# Geiger_Pwr_LM3478.net
KiCad netlist of a schematic drawn in Altium Designer
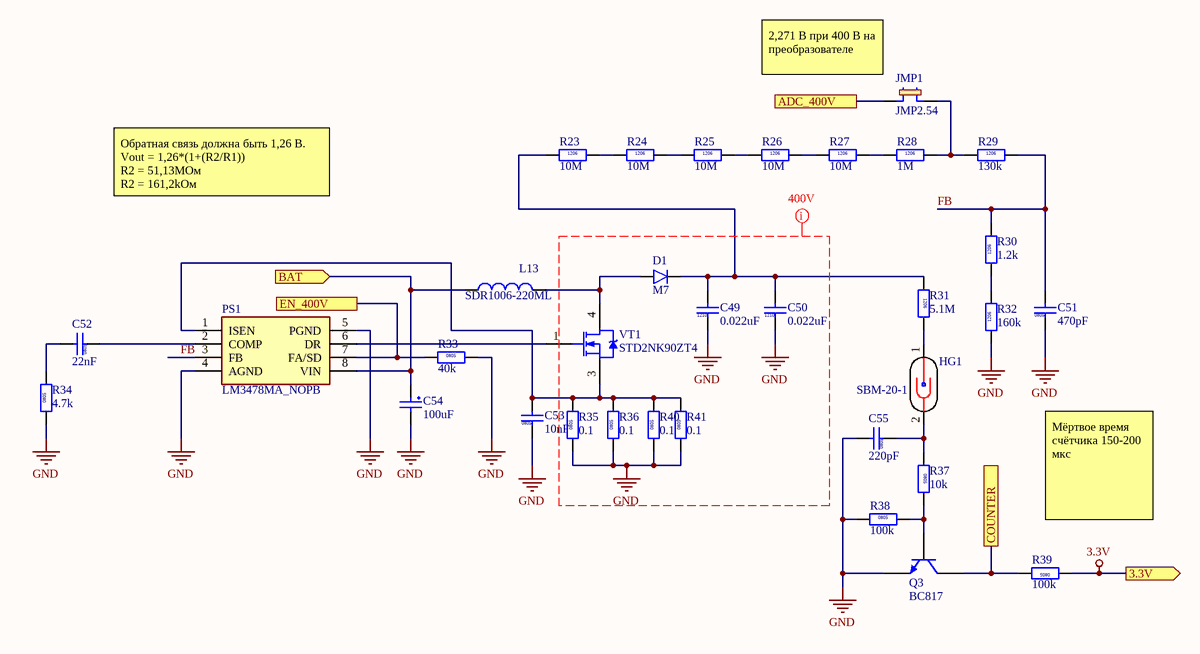
[diagram p0: Geiger_Pwr_LM3478.SchDoc]

(export (version "E")
  (design (tool "Eeschema 10.0.6"))
  (components
    (comp (ref "C49")
      (value "0.022uF")
      (footprint "CAPC3225-1210L")
      (description "Capacitor 1210")
      (fields (field (name "Comment") "CAPC_1210"))
      (libsource (lib "Passive") (part "CAPC_1210"))
    )
    (comp (ref "C50")
      (value "0.022uF")
      (footprint "CAPC3225-1210L")
      (description "Capacitor 1210")
      (fields (field (name "Comment") "CAPC_1210"))
      (libsource (lib "Passive") (part "CAPC_1210"))
    )
    (comp (ref "C51")
      (value "470pF")
      (footprint "CAPC2012-0805M")
      (description "Capacitor 0805")
      (fields (field (name "Comment") "CAPC_0805"))
      (libsource (lib "Passive") (part "CAPC_0805"))
    )
    (comp (ref "C52")
      (value "22nF")
      (footprint "CAPC2012-0805M")
      (description "Capacitor 0805")
      (fields (field (name "Comment") "CAPC_0805"))
      (libsource (lib "Passive") (part "CAPC_0805"))
    )
    (comp (ref "C53")
      (value "10nF")
      (footprint "CAPC2012-0805M")
      (description "Capacitor 0805")
      (fields (field (name "Comment") "CAPC_0805"))
      (libsource (lib "Passive") (part "CAPC_0805"))
    )
    (comp (ref "C54")
      (value "100uF")
      (footprint "ECAP511")
      (description "Capacitor electrolytic 2.5 mm pitch, 5*11 body")
      (fields (field (name "Comment") "ECAP-511"))
      (libsource (lib "Passive") (part "ECAP-511"))
    )
    (comp (ref "C55")
      (value "220pF")
      (footprint "CAPC2012-0805M")
      (description "Capacitor 0805")
      (fields (field (name "Comment") "CAPC_0805"))
      (libsource (lib "Passive") (part "CAPC_0805"))
    )
    (comp (ref "D1")
      (value "M7")
      (footprint "DIOM5026X262N")
      (description "Diode")
      (fields (field (name "MANUFACTURER_PART_NUMBER") "SS34A"))
      (libsource (lib "M7 diode") (part "M7"))
    )
    (comp (ref "HG1")
      (value "SBM-20-1")
      (footprint "SBM-20-1")
      (libsource (lib "Bogdanov") (part "SBM-20-1"))
    )
    (comp (ref "JMP1")
      (value "JMP2.54")
      (footprint "JMP2.54")
      (description "2.54mm single jumper")
      (libsource (lib "Connectors") (part "JMP2.54"))
    )
    (comp (ref "L13")
      (value "SDR1006-220ML")
      (footprint "Bogdanov:SDR1006")
      (description "Connector")
      (fields
        (field (name "MOUSER PART NUMBER") "652-SDR1006-220ML")
        (field (name "RS PART NUMBER") "7361349P")
      )
      (libsource (lib "Bogdanov") (part "SDR1006-220ML"))
    )
    (comp (ref "PS1")
      (value "LM3478MA_NOPB")
      (footprint "SamacSys:SOIC127P600X175-8N")
      (description "Power Supply")
      (fields
        (field (name "MANUFACTURER_PART_NUMBER") "LM3478MA/NOPB")
        (field (name "MOUSER PART NUMBER") "926-LM3478MA/NOPB")
      )
      (libsource (lib "*") (part "LM3478MA_NOPB"))
    )
    (comp (ref "Q3")
      (value "BC817")
      (footprint "SOT23-3M")
      (description "BC817 NPN Transistor")
      (libsource (lib "Discrete") (part "BC817"))
    )
    (comp (ref "R23")
      (value "10M")
      (footprint "RESC3216-1206M")
      (description "Resistor 1206")
      (fields (field (name "Comment") "RESC_1206_R"))
      (libsource (lib "Passive") (part "RESC_1206_R"))
    )
    (comp (ref "R24")
      (value "10M")
      (footprint "RESC3216-1206M")
      (description "Resistor 1206")
      (fields (field (name "Comment") "RESC_1206_R"))
      (libsource (lib "Passive") (part "RESC_1206_R"))
    )
    (comp (ref "R25")
      (value "10M")
      (footprint "RESC3216-1206M")
      (description "Resistor 1206")
      (fields (field (name "Comment") "RESC_1206_R"))
      (libsource (lib "Passive") (part "RESC_1206_R"))
    )
    (comp (ref "R26")
      (value "10M")
      (footprint "RESC3216-1206M")
      (description "Resistor 1206")
      (fields (field (name "Comment") "RESC_1206_R"))
      (libsource (lib "Passive") (part "RESC_1206_R"))
    )
    (comp (ref "R27")
      (value "10M")
      (footprint "RESC3216-1206M")
      (description "Resistor 1206")
      (fields (field (name "Comment") "RESC_1206_R"))
      (libsource (lib "Passive") (part "RESC_1206_R"))
    )
    (comp (ref "R28")
      (value "1M")
      (footprint "RESC3216-1206M")
      (description "Resistor 1206")
      (fields (field (name "Comment") "RESC_1206_R"))
      (libsource (lib "Passive") (part "RESC_1206_R"))
    )
    (comp (ref "R29")
      (value "130k")
      (footprint "RESC3216-1206M")
      (description "Resistor 1206")
      (fields (field (name "Comment") "RESC_1206_R"))
      (libsource (lib "Passive") (part "RESC_1206_R"))
    )
    (comp (ref "R30")
      (value "1.2k")
      (footprint "RESC3216-1206M")
      (description "Resistor 1206")
      (fields (field (name "Comment") "RESC_1206_R"))
      (libsource (lib "") (part "RESC_1206_R_1"))
    )
    (comp (ref "R31")
      (value "5.1M")
      (footprint "RESC3216-1206M")
      (description "Resistor 1206")
      (fields (field (name "Comment") "RESC_1206_R"))
      (libsource (lib "") (part "RESC_1206_R_2"))
    )
    (comp (ref "R32")
      (value "160k")
      (footprint "RESC3216-1206M")
      (description "Resistor 1206")
      (fields (field (name "Comment") "RESC_1206_R"))
      (libsource (lib "") (part "RESC_1206_R_1"))
    )
    (comp (ref "R33")
      (value "40k")
      (footprint "RESC2012-0805M")
      (description "Resistor 0805")
      (fields (field (name "Comment") "RESC_0805_R"))
      (libsource (lib "Passive") (part "RESC_0805_R"))
    )
    (comp (ref "R34")
      (value "4.7k")
      (footprint "RESC2012-0805M")
      (description "Resistor 0805")
      (fields (field (name "Comment") "RESC_0805_R"))
      (libsource (lib "") (part "RESC_0805_R_1"))
    )
    (comp (ref "R35")
      (value "0.1")
      (footprint "RESC2012-0805M")
      (description "Resistor 0805")
      (fields (field (name "Comment") "RESC_0805_R"))
      (libsource (lib "") (part "RESC_0805_R_1"))
    )
    (comp (ref "R36")
      (value "0.1")
      (footprint "RESC2012-0805M")
      (description "Resistor 0805")
      (fields (field (name "Comment") "RESC_0805_R"))
      (libsource (lib "") (part "RESC_0805_R_1"))
    )
    (comp (ref "R37")
      (value "10k")
      (footprint "RESC2012-0805M")
      (description "Resistor 0805")
      (fields (field (name "Comment") "RESC_0805_R"))
      (libsource (lib "") (part "RESC_0805_R_2"))
    )
    (comp (ref "R38")
      (value "100k")
      (footprint "RESC2012-0805M")
      (description "Resistor 0805")
      (fields (field (name "Comment") "RESC_0805_R"))
      (libsource (lib "Passive") (part "RESC_0805_R"))
    )
    (comp (ref "R39")
      (value "100k")
      (footprint "RESC2012-0805M")
      (description "Resistor 0805")
      (fields (field (name "Comment") "RESC_0805_R"))
      (libsource (lib "") (part "RESC_0805_R_3"))
    )
    (comp (ref "R40")
      (value "0.1")
      (footprint "RESC2012-0805M")
      (description "Resistor 0805")
      (fields (field (name "Comment") "RESC_0805_R"))
      (libsource (lib "") (part "RESC_0805_R_1"))
    )
    (comp (ref "R41")
      (value "0.1")
      (footprint "RESC2012-0805M")
      (description "Resistor 0805")
      (fields (field (name "Comment") "RESC_0805_R"))
      (libsource (lib "") (part "RESC_0805_R_1"))
    )
    (comp (ref "VT1")
      (value "STD2NK90ZT4")
      (footprint "SamacSys:TO228P972X240-3N")
      (description "Integrated Circuit")
      (fields (field (name "MOUSER PART NUMBER") "511-STD2NK90Z") (field (name "RS PART NUMBER") "6875100P"))
      (libsource (lib "Bogdanov") (part "STD2NK90ZT4"))
    )
  )
  (nets
    (net (code "1") (name "/ADC_400V") (class "Default")
      (node (ref "JMP1") (pin "1") (pinfunction "1_1") (pintype "power_in"))
    )
    (net (code "2") (name "/BAT") (class "Default")
      (node (ref "C54") (pin "1") (pinfunction "1_1") (pintype "passive"))
      (node (ref "L13") (pin "1") (pinfunction "1_1") (pintype "passive"))
      (node (ref "PS1") (pin "8") (pinfunction "VIN_8") (pintype "passive"))
    )
    (net (code "3") (name "/COUNTER") (class "Default")
      (node (ref "Q3") (pin "3") (pinfunction "C_3") (pintype "passive"))
      (node (ref "R39") (pin "2") (pinfunction "2_2") (pintype "passive"))
    )
    (net (code "4") (name "/EN_400V") (class "Default")
      (node (ref "PS1") (pin "7") (pinfunction "FA/SD_7") (pintype "passive"))
      (node (ref "R33") (pin "1") (pinfunction "1_1") (pintype "passive"))
    )
    (net (code "5") (name "/FB") (class "Default")
      (node (ref "C51") (pin "2") (pinfunction "2_2") (pintype "passive"))
      (node (ref "PS1") (pin "3") (pinfunction "FB_3") (pintype "passive"))
      (node (ref "R29") (pin "2") (pinfunction "2_2") (pintype "passive"))
      (node (ref "R30") (pin "2") (pinfunction "2_2") (pintype "passive"))
    )
    (net (code "6") (name "3.3V") (class "Default")
      (node (ref "R39") (pin "1") (pinfunction "1_1") (pintype "passive"))
    )
    (net (code "7") (name "GND") (class "Default")
      (node (ref "C49") (pin "1") (pinfunction "1_1") (pintype "passive"))
      (node (ref "C50") (pin "1") (pinfunction "1_1") (pintype "passive"))
      (node (ref "C51") (pin "1") (pinfunction "1_1") (pintype "passive"))
      (node (ref "C53") (pin "1") (pinfunction "1_1") (pintype "passive"))
      (node (ref "C54") (pin "2") (pinfunction "2_2") (pintype "passive"))
      (node (ref "C55") (pin "2") (pinfunction "2_2") (pintype "passive"))
      (node (ref "PS1") (pin "4") (pinfunction "AGND_4") (pintype "passive"))
      (node (ref "PS1") (pin "5") (pinfunction "PGND_5") (pintype "passive"))
      (node (ref "Q3") (pin "2") (pinfunction "E_2") (pintype "passive"))
      (node (ref "R32") (pin "1") (pinfunction "1_1") (pintype "passive"))
      (node (ref "R33") (pin "2") (pinfunction "2_2") (pintype "passive"))
      (node (ref "R34") (pin "1") (pinfunction "1_1") (pintype "passive"))
      (node (ref "R35") (pin "1") (pinfunction "1_1") (pintype "passive"))
      (node (ref "R36") (pin "1") (pinfunction "1_1") (pintype "passive"))
      (node (ref "R38") (pin "1") (pinfunction "1_1") (pintype "passive"))
      (node (ref "R40") (pin "1") (pinfunction "1_1") (pintype "passive"))
      (node (ref "R41") (pin "1") (pinfunction "1_1") (pintype "passive"))
    )
    (net (code "8") (name "Net-(C52-Pad2)") (class "Default")
      (node (ref "C52") (pin "2") (pinfunction "2_2") (pintype "passive"))
      (node (ref "R34") (pin "2") (pinfunction "2_2") (pintype "passive"))
    )
    (net (code "9") (name "Net-(D1-A)") (class "Default")
      (node (ref "D1") (pin "2") (pinfunction "A_2") (pintype "passive"))
      (node (ref "L13") (pin "2") (pinfunction "2_2") (pintype "passive"))
      (node (ref "VT1") (pin "4") (pinfunction "D_4") (pintype "passive"))
    )
    (net (code "10") (name "Net-(D1-K)") (class "Default")
      (node (ref "C49") (pin "2") (pinfunction "2_2") (pintype "passive"))
      (node (ref "C50") (pin "2") (pinfunction "2_2") (pintype "passive"))
      (node (ref "D1") (pin "1") (pinfunction "K_1") (pintype "passive"))
      (node (ref "R23") (pin "1") (pinfunction "1_1") (pintype "passive"))
      (node (ref "R31") (pin "1") (pinfunction "1_1") (pintype "passive"))
    )
    (net (code "11") (name "Net-(HG1-A)") (class "Default")
      (node (ref "HG1") (pin "1") (pinfunction "A_1") (pintype "passive"))
      (node (ref "R31") (pin "2") (pinfunction "2_2") (pintype "passive"))
    )
    (net (code "12") (name "Net-(HG1-K)") (class "Default")
      (node (ref "C55") (pin "1") (pinfunction "1_1") (pintype "passive"))
      (node (ref "HG1") (pin "2") (pinfunction "K_2") (pintype "passive"))
      (node (ref "R37") (pin "1") (pinfunction "1_1") (pintype "passive"))
    )
    (net (code "13") (name "Net-(JMP1-Pad2)") (class "Default")
      (node (ref "JMP1") (pin "2") (pinfunction "2_2") (pintype "power_in"))
      (node (ref "R28") (pin "2") (pinfunction "2_2") (pintype "passive"))
      (node (ref "R29") (pin "1") (pinfunction "1_1") (pintype "passive"))
    )
    (net (code "14") (name "Net-(PS1-COMP)") (class "Default")
      (node (ref "C52") (pin "1") (pinfunction "1_1") (pintype "passive"))
      (node (ref "PS1") (pin "2") (pinfunction "COMP_2") (pintype "passive"))
    )
    (net (code "15") (name "Net-(PS1-DR)") (class "Default")
      (node (ref "PS1") (pin "6") (pinfunction "DR_6") (pintype "passive"))
      (node (ref "VT1") (pin "1") (pinfunction "G_1") (pintype "passive"))
    )
    (net (code "16") (name "Net-(PS1-ISEN)") (class "Default")
      (node (ref "C53") (pin "2") (pinfunction "2_2") (pintype "passive"))
      (node (ref "PS1") (pin "1") (pinfunction "ISEN_1") (pintype "passive"))
      (node (ref "R35") (pin "2") (pinfunction "2_2") (pintype "passive"))
      (node (ref "R36") (pin "2") (pinfunction "2_2") (pintype "passive"))
      (node (ref "R40") (pin "2") (pinfunction "2_2") (pintype "passive"))
      (node (ref "R41") (pin "2") (pinfunction "2_2") (pintype "passive"))
      (node (ref "VT1") (pin "3") (pinfunction "S_3") (pintype "passive"))
    )
    (net (code "17") (name "Net-(Q3-B)") (class "Default")
      (node (ref "Q3") (pin "1") (pinfunction "B_1") (pintype "passive"))
      (node (ref "R37") (pin "2") (pinfunction "2_2") (pintype "passive"))
      (node (ref "R38") (pin "2") (pinfunction "2_2") (pintype "passive"))
    )
    (net (code "18") (name "Net-(R23-Pad2)") (class "Default")
      (node (ref "R23") (pin "2") (pinfunction "2_2") (pintype "passive"))
      (node (ref "R24") (pin "1") (pinfunction "1_1") (pintype "passive"))
    )
    (net (code "19") (name "Net-(R24-Pad2)") (class "Default")
      (node (ref "R24") (pin "2") (pinfunction "2_2") (pintype "passive"))
      (node (ref "R25") (pin "1") (pinfunction "1_1") (pintype "passive"))
    )
    (net (code "20") (name "Net-(R25-Pad2)") (class "Default")
      (node (ref "R25") (pin "2") (pinfunction "2_2") (pintype "passive"))
      (node (ref "R26") (pin "1") (pinfunction "1_1") (pintype "passive"))
    )
    (net (code "21") (name "Net-(R26-Pad2)") (class "Default")
      (node (ref "R26") (pin "2") (pinfunction "2_2") (pintype "passive"))
      (node (ref "R27") (pin "1") (pinfunction "1_1") (pintype "passive"))
    )
    (net (code "22") (name "Net-(R27-Pad2)") (class "Default")
      (node (ref "R27") (pin "2") (pinfunction "2_2") (pintype "passive"))
      (node (ref "R28") (pin "1") (pinfunction "1_1") (pintype "passive"))
    )
    (net (code "23") (name "Net-(R30-Pad1)") (class "Default")
      (node (ref "R30") (pin "1") (pinfunction "1_1") (pintype "passive"))
      (node (ref "R32") (pin "2") (pinfunction "2_2") (pintype "passive"))
    )
  )
)
